# Zhurong.net
KiCad netlist of a schematic drawn in EasyEDA Pro
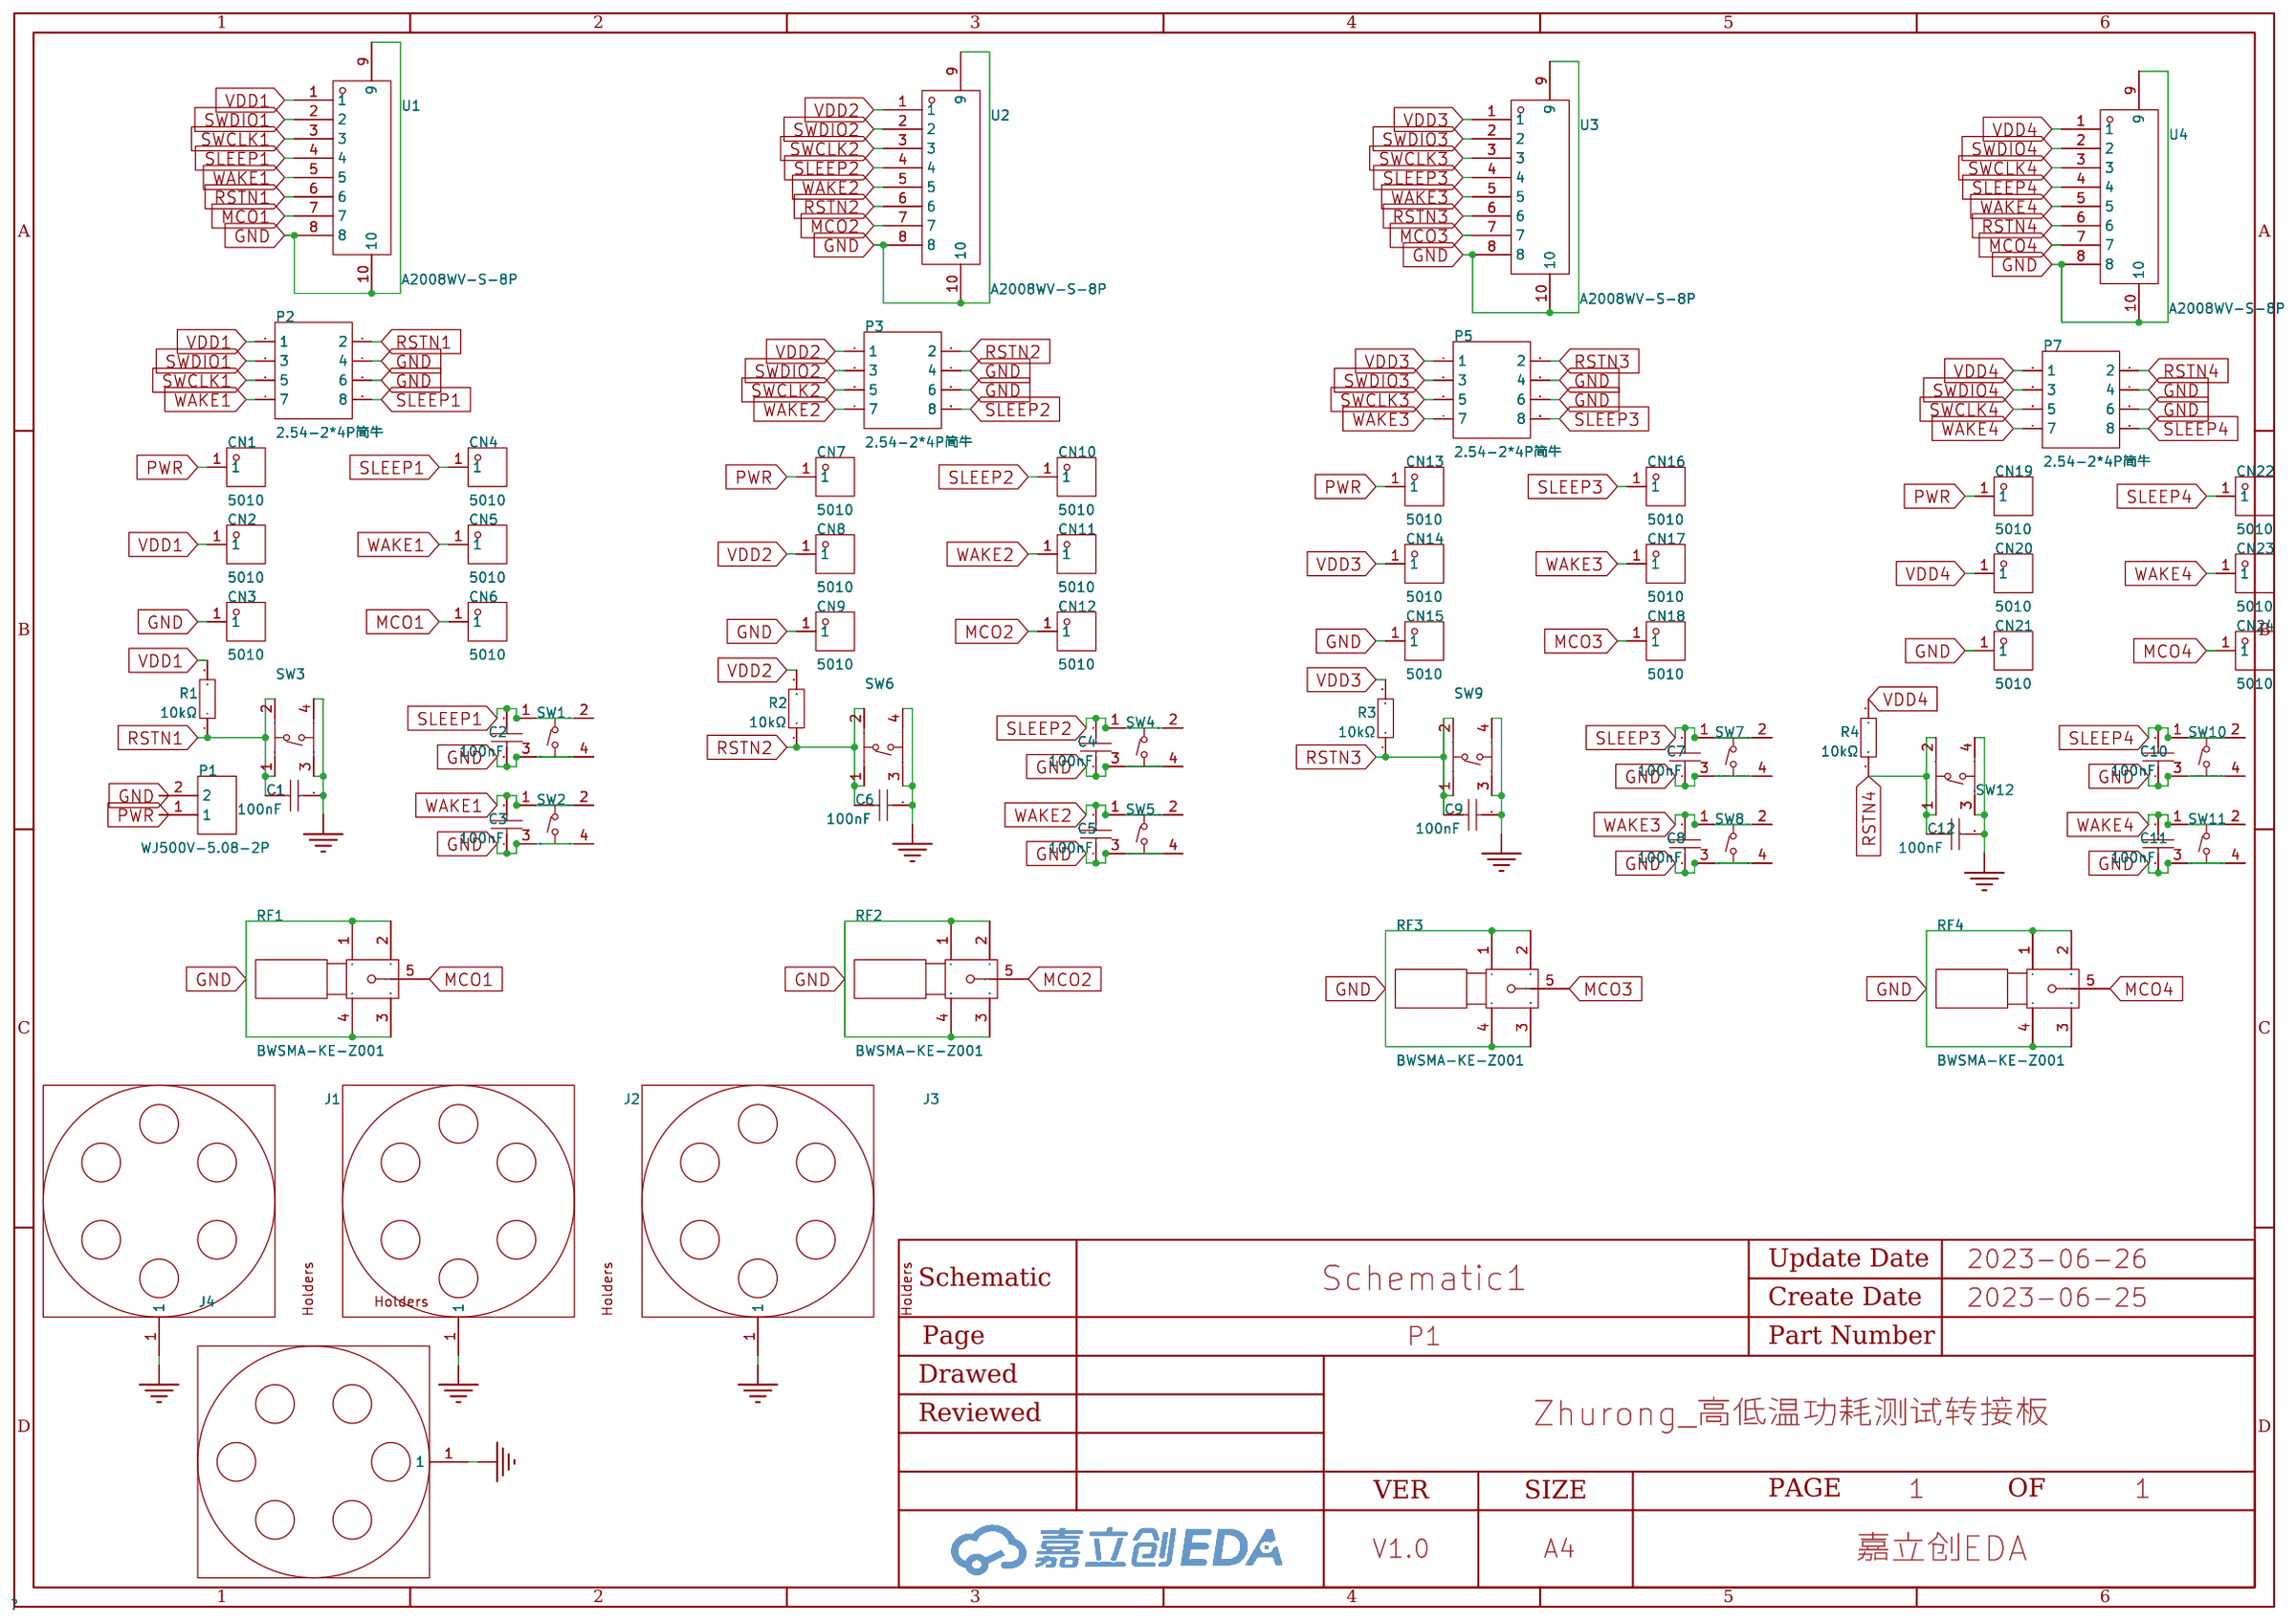
[diagram p0: schematic sheet]

(export (version "E")
  (design (tool "Eeschema 10.0.6"))
  (components
    (comp (ref "C1")
      (value "100nF")
      (footprint "easyedapro:C0603")
      (description "容值:100nF;精度:±10%;额定电压:50V;材质(温度系数):X7R;")
      (fields (field (name "Manufacturer Part") "0603B104K500NT") (field (name "Manufacturer") "FH(风华)"))
      (libsource (lib "easyedapro") (part "0603B104K500NT"))
    )
    (comp (ref "C2")
      (value "100nF")
      (footprint "easyedapro:C0603")
      (description "容值:100nF;精度:±10%;额定电压:50V;材质(温度系数):X7R;")
      (fields (field (name "Manufacturer Part") "0603B104K500NT") (field (name "Manufacturer") "FH(风华)"))
      (libsource (lib "easyedapro") (part "0603B104K500NT"))
    )
    (comp (ref "C3")
      (value "100nF")
      (footprint "easyedapro:C0603")
      (description "容值:100nF;精度:±10%;额定电压:50V;材质(温度系数):X7R;")
      (fields (field (name "Manufacturer Part") "0603B104K500NT") (field (name "Manufacturer") "FH(风华)"))
      (libsource (lib "easyedapro") (part "0603B104K500NT"))
    )
    (comp (ref "C4")
      (value "100nF")
      (footprint "easyedapro:C0603")
      (description "容值:100nF;精度:±10%;额定电压:50V;材质(温度系数):X7R;")
      (fields (field (name "Manufacturer Part") "0603B104K500NT") (field (name "Manufacturer") "FH(风华)"))
      (libsource (lib "easyedapro") (part "0603B104K500NT"))
    )
    (comp (ref "C5")
      (value "100nF")
      (footprint "easyedapro:C0603")
      (description "容值:100nF;精度:±10%;额定电压:50V;材质(温度系数):X7R;")
      (fields (field (name "Manufacturer Part") "0603B104K500NT") (field (name "Manufacturer") "FH(风华)"))
      (libsource (lib "easyedapro") (part "0603B104K500NT"))
    )
    (comp (ref "C6")
      (value "100nF")
      (footprint "easyedapro:C0603")
      (description "容值:100nF;精度:±10%;额定电压:50V;材质(温度系数):X7R;")
      (fields (field (name "Manufacturer Part") "0603B104K500NT") (field (name "Manufacturer") "FH(风华)"))
      (libsource (lib "easyedapro") (part "0603B104K500NT"))
    )
    (comp (ref "C7")
      (value "100nF")
      (footprint "easyedapro:C0603")
      (description "容值:100nF;精度:±10%;额定电压:50V;材质(温度系数):X7R;")
      (fields (field (name "Manufacturer Part") "0603B104K500NT") (field (name "Manufacturer") "FH(风华)"))
      (libsource (lib "easyedapro") (part "0603B104K500NT"))
    )
    (comp (ref "C8")
      (value "100nF")
      (footprint "easyedapro:C0603")
      (description "容值:100nF;精度:±10%;额定电压:50V;材质(温度系数):X7R;")
      (fields (field (name "Manufacturer Part") "0603B104K500NT") (field (name "Manufacturer") "FH(风华)"))
      (libsource (lib "easyedapro") (part "0603B104K500NT"))
    )
    (comp (ref "C9")
      (value "100nF")
      (footprint "easyedapro:C0603")
      (description "容值:100nF;精度:±10%;额定电压:50V;材质(温度系数):X7R;")
      (fields (field (name "Manufacturer Part") "0603B104K500NT") (field (name "Manufacturer") "FH(风华)"))
      (libsource (lib "easyedapro") (part "0603B104K500NT"))
    )
    (comp (ref "C10")
      (value "100nF")
      (footprint "easyedapro:C0603")
      (description "容值:100nF;精度:±10%;额定电压:50V;材质(温度系数):X7R;")
      (fields (field (name "Manufacturer Part") "0603B104K500NT") (field (name "Manufacturer") "FH(风华)"))
      (libsource (lib "easyedapro") (part "0603B104K500NT"))
    )
    (comp (ref "C11")
      (value "100nF")
      (footprint "easyedapro:C0603")
      (description "容值:100nF;精度:±10%;额定电压:50V;材质(温度系数):X7R;")
      (fields (field (name "Manufacturer Part") "0603B104K500NT") (field (name "Manufacturer") "FH(风华)"))
      (libsource (lib "easyedapro") (part "0603B104K500NT"))
    )
    (comp (ref "C12")
      (value "100nF")
      (footprint "easyedapro:C0603")
      (description "容值:100nF;精度:±10%;额定电压:50V;材质(温度系数):X7R;")
      (fields (field (name "Manufacturer Part") "0603B104K500NT") (field (name "Manufacturer") "FH(风华)"))
      (libsource (lib "easyedapro") (part "0603B104K500NT"))
    )
    (comp (ref "CN1")
      (value "5010")
      (footprint "easyedapro:TESTPOINT-TH_BD3.2")
      (fields (field (name "Manufacturer") "Keystone"))
      (libsource (lib "easyedapro") (part "5010"))
    )
    (comp (ref "CN2")
      (value "5010")
      (footprint "easyedapro:TESTPOINT-TH_BD3.2")
      (fields (field (name "Manufacturer") "Keystone"))
      (libsource (lib "easyedapro") (part "5010"))
    )
    (comp (ref "CN3")
      (value "5010")
      (footprint "easyedapro:TESTPOINT-TH_BD3.2")
      (fields (field (name "Manufacturer") "Keystone"))
      (libsource (lib "easyedapro") (part "5010"))
    )
    (comp (ref "CN4")
      (value "5010")
      (footprint "easyedapro:TESTPOINT-TH_BD3.2")
      (fields (field (name "Manufacturer") "Keystone"))
      (libsource (lib "easyedapro") (part "5010"))
    )
    (comp (ref "CN5")
      (value "5010")
      (footprint "easyedapro:TESTPOINT-TH_BD3.2")
      (fields (field (name "Manufacturer") "Keystone"))
      (libsource (lib "easyedapro") (part "5010"))
    )
    (comp (ref "CN6")
      (value "5010")
      (footprint "easyedapro:TESTPOINT-TH_BD3.2")
      (fields (field (name "Manufacturer") "Keystone"))
      (libsource (lib "easyedapro") (part "5010"))
    )
    (comp (ref "CN7")
      (value "5010")
      (footprint "easyedapro:TESTPOINT-TH_BD3.2")
      (fields (field (name "Manufacturer") "Keystone"))
      (libsource (lib "easyedapro") (part "5010"))
    )
    (comp (ref "CN8")
      (value "5010")
      (footprint "easyedapro:TESTPOINT-TH_BD3.2")
      (fields (field (name "Manufacturer") "Keystone"))
      (libsource (lib "easyedapro") (part "5010"))
    )
    (comp (ref "CN9")
      (value "5010")
      (footprint "easyedapro:TESTPOINT-TH_BD3.2")
      (fields (field (name "Manufacturer") "Keystone"))
      (libsource (lib "easyedapro") (part "5010"))
    )
    (comp (ref "CN10")
      (value "5010")
      (footprint "easyedapro:TESTPOINT-TH_BD3.2")
      (fields (field (name "Manufacturer") "Keystone"))
      (libsource (lib "easyedapro") (part "5010"))
    )
    (comp (ref "CN11")
      (value "5010")
      (footprint "easyedapro:TESTPOINT-TH_BD3.2")
      (fields (field (name "Manufacturer") "Keystone"))
      (libsource (lib "easyedapro") (part "5010"))
    )
    (comp (ref "CN12")
      (value "5010")
      (footprint "easyedapro:TESTPOINT-TH_BD3.2")
      (fields (field (name "Manufacturer") "Keystone"))
      (libsource (lib "easyedapro") (part "5010"))
    )
    (comp (ref "CN13")
      (value "5010")
      (footprint "easyedapro:TESTPOINT-TH_BD3.2")
      (fields (field (name "Manufacturer") "Keystone"))
      (libsource (lib "easyedapro") (part "5010"))
    )
    (comp (ref "CN14")
      (value "5010")
      (footprint "easyedapro:TESTPOINT-TH_BD3.2")
      (fields (field (name "Manufacturer") "Keystone"))
      (libsource (lib "easyedapro") (part "5010"))
    )
    (comp (ref "CN15")
      (value "5010")
      (footprint "easyedapro:TESTPOINT-TH_BD3.2")
      (fields (field (name "Manufacturer") "Keystone"))
      (libsource (lib "easyedapro") (part "5010"))
    )
    (comp (ref "CN16")
      (value "5010")
      (footprint "easyedapro:TESTPOINT-TH_BD3.2")
      (fields (field (name "Manufacturer") "Keystone"))
      (libsource (lib "easyedapro") (part "5010"))
    )
    (comp (ref "CN17")
      (value "5010")
      (footprint "easyedapro:TESTPOINT-TH_BD3.2")
      (fields (field (name "Manufacturer") "Keystone"))
      (libsource (lib "easyedapro") (part "5010"))
    )
    (comp (ref "CN18")
      (value "5010")
      (footprint "easyedapro:TESTPOINT-TH_BD3.2")
      (fields (field (name "Manufacturer") "Keystone"))
      (libsource (lib "easyedapro") (part "5010"))
    )
    (comp (ref "CN19")
      (value "5010")
      (footprint "easyedapro:TESTPOINT-TH_BD3.2")
      (fields (field (name "Manufacturer") "Keystone"))
      (libsource (lib "easyedapro") (part "5010"))
    )
    (comp (ref "CN20")
      (value "5010")
      (footprint "easyedapro:TESTPOINT-TH_BD3.2")
      (fields (field (name "Manufacturer") "Keystone"))
      (libsource (lib "easyedapro") (part "5010"))
    )
    (comp (ref "CN21")
      (value "5010")
      (footprint "easyedapro:TESTPOINT-TH_BD3.2")
      (fields (field (name "Manufacturer") "Keystone"))
      (libsource (lib "easyedapro") (part "5010"))
    )
    (comp (ref "CN22")
      (value "5010")
      (footprint "easyedapro:TESTPOINT-TH_BD3.2")
      (fields (field (name "Manufacturer") "Keystone"))
      (libsource (lib "easyedapro") (part "5010"))
    )
    (comp (ref "CN23")
      (value "5010")
      (footprint "easyedapro:TESTPOINT-TH_BD3.2")
      (fields (field (name "Manufacturer") "Keystone"))
      (libsource (lib "easyedapro") (part "5010"))
    )
    (comp (ref "CN24")
      (value "5010")
      (footprint "easyedapro:TESTPOINT-TH_BD3.2")
      (fields (field (name "Manufacturer") "Keystone"))
      (libsource (lib "easyedapro") (part "5010"))
    )
    (comp (ref "J1")
      (value "~")
      (footprint "easyedapro:DEMO板安装孔")
      (libsource (lib "easyedapro") (part "螺孔_3.1X6MM"))
    )
    (comp (ref "J2")
      (value "~")
      (footprint "easyedapro:DEMO板安装孔")
      (libsource (lib "easyedapro") (part "螺孔_3.1X6MM"))
    )
    (comp (ref "J3")
      (value "~")
      (footprint "easyedapro:DEMO板安装孔")
      (libsource (lib "easyedapro") (part "螺孔_3.1X6MM"))
    )
    (comp (ref "J4")
      (value "~")
      (footprint "easyedapro:DEMO板安装孔")
      (libsource (lib "easyedapro") (part "螺孔_3.1X6MM"))
    )
    (comp (ref "P1")
      (value "WJ500V-5.08-2P")
      (footprint "easyedapro:CONN-TH_2P-P5.00_WJ500V-5.08-2P")
      (fields (field (name "Manufacturer") "KANGNEX(康奈克斯电气)"))
      (libsource (lib "easyedapro") (part "WJ500V-5.08-2P-14-00A"))
    )
    (comp (ref "P2")
      (value "2.54-2*4P简牛")
      (footprint "easyedapro:IDC-TH_8P-P2.54-V-R2-C4-S2.54")
      (description "连接器类型:简牛座;每排PIN数:4;结构:2x4P;排数:2;间距:2.54mm;行距:2.54mm;封装形式:直插;触头材质:-;触头镀层:-;")
      (fields (field (name "Manufacturer") "BOOMELE(博穆精密)"))
      (libsource (lib "easyedapro") (part "HDR-IDC-2.54-2X4P"))
    )
    (comp (ref "P3")
      (value "2.54-2*4P简牛")
      (footprint "easyedapro:IDC-TH_8P-P2.54-V-R2-C4-S2.54")
      (description "连接器类型:简牛座;每排PIN数:4;结构:2x4P;排数:2;间距:2.54mm;行距:2.54mm;封装形式:直插;触头材质:-;触头镀层:-;")
      (fields (field (name "Manufacturer") "BOOMELE(博穆精密)"))
      (libsource (lib "easyedapro") (part "HDR-IDC-2.54-2X4P"))
    )
    (comp (ref "P5")
      (value "2.54-2*4P简牛")
      (footprint "easyedapro:IDC-TH_8P-P2.54-V-R2-C4-S2.54")
      (description "连接器类型:简牛座;每排PIN数:4;结构:2x4P;排数:2;间距:2.54mm;行距:2.54mm;封装形式:直插;触头材质:-;触头镀层:-;")
      (fields (field (name "Manufacturer") "BOOMELE(博穆精密)"))
      (libsource (lib "easyedapro") (part "HDR-IDC-2.54-2X4P"))
    )
    (comp (ref "P7")
      (value "2.54-2*4P简牛")
      (footprint "easyedapro:IDC-TH_8P-P2.54-V-R2-C4-S2.54")
      (description "连接器类型:简牛座;每排PIN数:4;结构:2x4P;排数:2;间距:2.54mm;行距:2.54mm;封装形式:直插;触头材质:-;触头镀层:-;")
      (fields (field (name "Manufacturer") "BOOMELE(博穆精密)"))
      (libsource (lib "easyedapro") (part "HDR-IDC-2.54-2X4P"))
    )
    (comp (ref "R1")
      (value "10kΩ")
      (footprint "easyedapro:R0805")
      (description "阻值:10kΩ;精度:±1%;功率:125mW;温度系数:±100ppm/°C;最大工作电压:150V;工作温度范围:-55°C~+155°C;")
      (fields (field (name "Manufacturer Part") "RC0805FR-0710KL") (field (name "Manufacturer") "YAGEO(国巨)"))
      (libsource (lib "easyedapro") (part "RC0805FR-0710KL"))
    )
    (comp (ref "R2")
      (value "10kΩ")
      (footprint "easyedapro:R0805")
      (description "阻值:10kΩ;精度:±1%;功率:125mW;温度系数:±100ppm/°C;最大工作电压:150V;工作温度范围:-55°C~+155°C;")
      (fields (field (name "Manufacturer Part") "RC0805FR-0710KL") (field (name "Manufacturer") "YAGEO(国巨)"))
      (libsource (lib "easyedapro") (part "RC0805FR-0710KL"))
    )
    (comp (ref "R3")
      (value "10kΩ")
      (footprint "easyedapro:R0805")
      (description "阻值:10kΩ;精度:±1%;功率:125mW;温度系数:±100ppm/°C;最大工作电压:150V;工作温度范围:-55°C~+155°C;")
      (fields (field (name "Manufacturer Part") "RC0805FR-0710KL") (field (name "Manufacturer") "YAGEO(国巨)"))
      (libsource (lib "easyedapro") (part "RC0805FR-0710KL"))
    )
    (comp (ref "R4")
      (value "10kΩ")
      (footprint "easyedapro:R0805")
      (description "阻值:10kΩ;精度:±1%;功率:125mW;温度系数:±100ppm/°C;最大工作电压:150V;工作温度范围:-55°C~+155°C;")
      (fields (field (name "Manufacturer Part") "RC0805FR-0710KL") (field (name "Manufacturer") "YAGEO(国巨)"))
      (libsource (lib "easyedapro") (part "RC0805FR-0710KL"))
    )
    (comp (ref "RF1")
      (value "BWSMA-KE-Z001")
      (footprint "easyedapro:SMA-TH_BWSMA-KE-Z001")
      (description "连接器类型:板端;射频系列:SMA;接口类型:内孔;端口数量:1;阻抗:50Ω;频率-最大值:12.4GHz;样式:正脚;接口直径:-;接口长度/高度:-;工作温度范围:-65°C~+165°C;")
      (fields (field (name "Manufacturer") "BAT WIRELESS(蝙蝠无线)"))
      (libsource (lib "easyedapro") (part "BWSMA-KE-Z001"))
    )
    (comp (ref "RF2")
      (value "BWSMA-KE-Z001")
      (footprint "easyedapro:SMA-TH_BWSMA-KE-Z001")
      (description "连接器类型:板端;射频系列:SMA;接口类型:内孔;端口数量:1;阻抗:50Ω;频率-最大值:12.4GHz;样式:正脚;接口直径:-;接口长度/高度:-;工作温度范围:-65°C~+165°C;")
      (fields (field (name "Manufacturer") "BAT WIRELESS(蝙蝠无线)"))
      (libsource (lib "easyedapro") (part "BWSMA-KE-Z001"))
    )
    (comp (ref "RF3")
      (value "BWSMA-KE-Z001")
      (footprint "easyedapro:SMA-TH_BWSMA-KE-Z001")
      (description "连接器类型:板端;射频系列:SMA;接口类型:内孔;端口数量:1;阻抗:50Ω;频率-最大值:12.4GHz;样式:正脚;接口直径:-;接口长度/高度:-;工作温度范围:-65°C~+165°C;")
      (fields (field (name "Manufacturer") "BAT WIRELESS(蝙蝠无线)"))
      (libsource (lib "easyedapro") (part "BWSMA-KE-Z001"))
    )
    (comp (ref "RF4")
      (value "BWSMA-KE-Z001")
      (footprint "easyedapro:SMA-TH_BWSMA-KE-Z001")
      (description "连接器类型:板端;射频系列:SMA;接口类型:内孔;端口数量:1;阻抗:50Ω;频率-最大值:12.4GHz;样式:正脚;接口直径:-;接口长度/高度:-;工作温度范围:-65°C~+165°C;")
      (fields (field (name "Manufacturer") "BAT WIRELESS(蝙蝠无线)"))
      (libsource (lib "easyedapro") (part "BWSMA-KE-Z001"))
    )
    (comp (ref "SW1")
      (value "YTS-C015-2K")
      (footprint "easyedapro:SW-SMD_4P-L4.5-W4.5-P3.00-LS6.8")
      (description "触点电流:50mA;额定电压(DC):12V;绝缘电阻:100MΩ;电路结构:单刀单掷;安装方式:立贴;作用力:260gf@±50gf;机械寿命:5万次;带支架:否;")
      (fields (field (name "Manufacturer") "YIYUAN(怡远)"))
      (libsource (lib "easyedapro") (part "YTS-C015-2K"))
    )
    (comp (ref "SW2")
      (value "YTS-C015-2K")
      (footprint "easyedapro:SW-SMD_4P-L4.5-W4.5-P3.00-LS6.8")
      (description "触点电流:50mA;额定电压(DC):12V;绝缘电阻:100MΩ;电路结构:单刀单掷;安装方式:立贴;作用力:260gf@±50gf;机械寿命:5万次;带支架:否;")
      (fields (field (name "Manufacturer") "YIYUAN(怡远)"))
      (libsource (lib "easyedapro") (part "YTS-C015-2K"))
    )
    (comp (ref "SW3")
      (value "YTS-C015-2K")
      (footprint "easyedapro:SW-SMD_4P-L4.5-W4.5-P3.00-LS6.8")
      (description "触点电流:50mA;额定电压(DC):12V;绝缘电阻:100MΩ;电路结构:单刀单掷;安装方式:立贴;作用力:260gf@±50gf;机械寿命:5万次;带支架:否;")
      (fields (field (name "Manufacturer") "YIYUAN(怡远)"))
      (libsource (lib "easyedapro") (part "YTS-C015-2K"))
    )
    (comp (ref "SW4")
      (value "YTS-C015-2K")
      (footprint "easyedapro:SW-SMD_4P-L4.5-W4.5-P3.00-LS6.8")
      (description "触点电流:50mA;额定电压(DC):12V;绝缘电阻:100MΩ;电路结构:单刀单掷;安装方式:立贴;作用力:260gf@±50gf;机械寿命:5万次;带支架:否;")
      (fields (field (name "Manufacturer") "YIYUAN(怡远)"))
      (libsource (lib "easyedapro") (part "YTS-C015-2K"))
    )
    (comp (ref "SW5")
      (value "YTS-C015-2K")
      (footprint "easyedapro:SW-SMD_4P-L4.5-W4.5-P3.00-LS6.8")
      (description "触点电流:50mA;额定电压(DC):12V;绝缘电阻:100MΩ;电路结构:单刀单掷;安装方式:立贴;作用力:260gf@±50gf;机械寿命:5万次;带支架:否;")
      (fields (field (name "Manufacturer") "YIYUAN(怡远)"))
      (libsource (lib "easyedapro") (part "YTS-C015-2K"))
    )
    (comp (ref "SW6")
      (value "YTS-C015-2K")
      (footprint "easyedapro:SW-SMD_4P-L4.5-W4.5-P3.00-LS6.8")
      (description "触点电流:50mA;额定电压(DC):12V;绝缘电阻:100MΩ;电路结构:单刀单掷;安装方式:立贴;作用力:260gf@±50gf;机械寿命:5万次;带支架:否;")
      (fields (field (name "Manufacturer") "YIYUAN(怡远)"))
      (libsource (lib "easyedapro") (part "YTS-C015-2K"))
    )
    (comp (ref "SW7")
      (value "YTS-C015-2K")
      (footprint "easyedapro:SW-SMD_4P-L4.5-W4.5-P3.00-LS6.8")
      (description "触点电流:50mA;额定电压(DC):12V;绝缘电阻:100MΩ;电路结构:单刀单掷;安装方式:立贴;作用力:260gf@±50gf;机械寿命:5万次;带支架:否;")
      (fields (field (name "Manufacturer") "YIYUAN(怡远)"))
      (libsource (lib "easyedapro") (part "YTS-C015-2K"))
    )
    (comp (ref "SW8")
      (value "YTS-C015-2K")
      (footprint "easyedapro:SW-SMD_4P-L4.5-W4.5-P3.00-LS6.8")
      (description "触点电流:50mA;额定电压(DC):12V;绝缘电阻:100MΩ;电路结构:单刀单掷;安装方式:立贴;作用力:260gf@±50gf;机械寿命:5万次;带支架:否;")
      (fields (field (name "Manufacturer") "YIYUAN(怡远)"))
      (libsource (lib "easyedapro") (part "YTS-C015-2K"))
    )
    (comp (ref "SW9")
      (value "YTS-C015-2K")
      (footprint "easyedapro:SW-SMD_4P-L4.5-W4.5-P3.00-LS6.8")
      (description "触点电流:50mA;额定电压(DC):12V;绝缘电阻:100MΩ;电路结构:单刀单掷;安装方式:立贴;作用力:260gf@±50gf;机械寿命:5万次;带支架:否;")
      (fields (field (name "Manufacturer") "YIYUAN(怡远)"))
      (libsource (lib "easyedapro") (part "YTS-C015-2K"))
    )
    (comp (ref "SW10")
      (value "YTS-C015-2K")
      (footprint "easyedapro:SW-SMD_4P-L4.5-W4.5-P3.00-LS6.8")
      (description "触点电流:50mA;额定电压(DC):12V;绝缘电阻:100MΩ;电路结构:单刀单掷;安装方式:立贴;作用力:260gf@±50gf;机械寿命:5万次;带支架:否;")
      (fields (field (name "Manufacturer") "YIYUAN(怡远)"))
      (libsource (lib "easyedapro") (part "YTS-C015-2K"))
    )
    (comp (ref "SW11")
      (value "YTS-C015-2K")
      (footprint "easyedapro:SW-SMD_4P-L4.5-W4.5-P3.00-LS6.8")
      (description "触点电流:50mA;额定电压(DC):12V;绝缘电阻:100MΩ;电路结构:单刀单掷;安装方式:立贴;作用力:260gf@±50gf;机械寿命:5万次;带支架:否;")
      (fields (field (name "Manufacturer") "YIYUAN(怡远)"))
      (libsource (lib "easyedapro") (part "YTS-C015-2K"))
    )
    (comp (ref "SW12")
      (value "YTS-C015-2K")
      (footprint "easyedapro:SW-SMD_4P-L4.5-W4.5-P3.00-LS6.8")
      (description "触点电流:50mA;额定电压(DC):12V;绝缘电阻:100MΩ;电路结构:单刀单掷;安装方式:立贴;作用力:260gf@±50gf;机械寿命:5万次;带支架:否;")
      (fields (field (name "Manufacturer") "YIYUAN(怡远)"))
      (libsource (lib "easyedapro") (part "YTS-C015-2K"))
    )
    (comp (ref "U1")
      (value "A2008WV-S-8P")
      (footprint "easyedapro:CONN-SMD_A2008WV-S-8P")
      (description "参考系列:PH;间距:2mm;插针结构:1x8P;排数:1;每排PIN数:8;行距:-;安装方式:-;触头材质:黄铜;")
      (fields (field (name "Manufacturer") "CJT(长江连接器)"))
      (libsource (lib "easyedapro") (part "A2008WV-S-8P"))
    )
    (comp (ref "U2")
      (value "A2008WV-S-8P")
      (footprint "easyedapro:CONN-SMD_A2008WV-S-8P")
      (description "参考系列:PH;间距:2mm;插针结构:1x8P;排数:1;每排PIN数:8;行距:-;安装方式:-;触头材质:黄铜;")
      (fields (field (name "Manufacturer") "CJT(长江连接器)"))
      (libsource (lib "easyedapro") (part "A2008WV-S-8P"))
    )
    (comp (ref "U3")
      (value "A2008WV-S-8P")
      (footprint "easyedapro:CONN-SMD_A2008WV-S-8P")
      (description "参考系列:PH;间距:2mm;插针结构:1x8P;排数:1;每排PIN数:8;行距:-;安装方式:-;触头材质:黄铜;")
      (fields (field (name "Manufacturer") "CJT(长江连接器)"))
      (libsource (lib "easyedapro") (part "A2008WV-S-8P"))
    )
    (comp (ref "U4")
      (value "A2008WV-S-8P")
      (footprint "easyedapro:CONN-SMD_A2008WV-S-8P")
      (description "参考系列:PH;间距:2mm;插针结构:1x8P;排数:1;每排PIN数:8;行距:-;安装方式:-;触头材质:黄铜;")
      (fields (field (name "Manufacturer") "CJT(长江连接器)"))
      (libsource (lib "easyedapro") (part "A2008WV-S-8P"))
    )
  )
  (nets
    (net (code "1") (name "GND") (class "Default")
      (node (ref "C1") (pin "2") (pinfunction "2_2") (pintype "input"))
      (node (ref "C10") (pin "1") (pinfunction "1_1") (pintype "input"))
      (node (ref "C11") (pin "1") (pinfunction "1_1") (pintype "input"))
      (node (ref "C12") (pin "2") (pinfunction "2_2") (pintype "input"))
      (node (ref "C2") (pin "1") (pinfunction "1_1") (pintype "input"))
      (node (ref "C3") (pin "1") (pinfunction "1_1") (pintype "input"))
      (node (ref "C4") (pin "1") (pinfunction "1_1") (pintype "input"))
      (node (ref "C5") (pin "1") (pinfunction "1_1") (pintype "input"))
      (node (ref "C6") (pin "2") (pinfunction "2_2") (pintype "input"))
      (node (ref "C7") (pin "1") (pinfunction "1_1") (pintype "input"))
      (node (ref "C8") (pin "1") (pinfunction "1_1") (pintype "input"))
      (node (ref "C9") (pin "2") (pinfunction "2_2") (pintype "input"))
      (node (ref "CN15") (pin "1") (pinfunction "1_1") (pintype "input"))
      (node (ref "CN21") (pin "1") (pinfunction "1_1") (pintype "input"))
      (node (ref "CN3") (pin "1") (pinfunction "1_1") (pintype "input"))
      (node (ref "CN9") (pin "1") (pinfunction "1_1") (pintype "input"))
      (node (ref "J1") (pin "1") (pinfunction "1_1") (pintype "input"))
      (node (ref "J2") (pin "1") (pinfunction "1_1") (pintype "input"))
      (node (ref "J3") (pin "1") (pinfunction "1_1") (pintype "input"))
      (node (ref "J4") (pin "1") (pinfunction "1_1") (pintype "input"))
      (node (ref "P1") (pin "2") (pinfunction "2_2") (pintype "input"))
      (node (ref "P2") (pin "4") (pinfunction "4_4") (pintype "input"))
      (node (ref "P2") (pin "6") (pinfunction "6_6") (pintype "input"))
      (node (ref "P3") (pin "4") (pinfunction "4_4") (pintype "input"))
      (node (ref "P3") (pin "6") (pinfunction "6_6") (pintype "input"))
      (node (ref "P5") (pin "4") (pinfunction "4_4") (pintype "input"))
      (node (ref "P5") (pin "6") (pinfunction "6_6") (pintype "input"))
      (node (ref "P7") (pin "4") (pinfunction "4_4") (pintype "input"))
      (node (ref "P7") (pin "6") (pinfunction "6_6") (pintype "input"))
      (node (ref "RF1") (pin "1") (pinfunction "1_1") (pintype "input"))
      (node (ref "RF1") (pin "2") (pinfunction "2_2") (pintype "input"))
      (node (ref "RF1") (pin "3") (pinfunction "3_3") (pintype "input"))
      (node (ref "RF1") (pin "4") (pinfunction "4_4") (pintype "input"))
      (node (ref "RF2") (pin "1") (pinfunction "1_1") (pintype "input"))
      (node (ref "RF2") (pin "2") (pinfunction "2_2") (pintype "input"))
      (node (ref "RF2") (pin "3") (pinfunction "3_3") (pintype "input"))
      (node (ref "RF2") (pin "4") (pinfunction "4_4") (pintype "input"))
      (node (ref "RF3") (pin "1") (pinfunction "1_1") (pintype "input"))
      (node (ref "RF3") (pin "2") (pinfunction "2_2") (pintype "input"))
      (node (ref "RF3") (pin "3") (pinfunction "3_3") (pintype "input"))
      (node (ref "RF3") (pin "4") (pinfunction "4_4") (pintype "input"))
      (node (ref "RF4") (pin "1") (pinfunction "1_1") (pintype "input"))
      (node (ref "RF4") (pin "2") (pinfunction "2_2") (pintype "input"))
      (node (ref "RF4") (pin "3") (pinfunction "3_3") (pintype "input"))
      (node (ref "RF4") (pin "4") (pinfunction "4_4") (pintype "input"))
      (node (ref "SW1") (pin "3") (pinfunction "3_3") (pintype "input"))
      (node (ref "SW1") (pin "4") (pinfunction "4_4") (pintype "input"))
      (node (ref "SW10") (pin "3") (pinfunction "3_3") (pintype "input"))
      (node (ref "SW10") (pin "4") (pinfunction "4_4") (pintype "input"))
      (node (ref "SW11") (pin "3") (pinfunction "3_3") (pintype "input"))
      (node (ref "SW11") (pin "4") (pinfunction "4_4") (pintype "input"))
      (node (ref "SW12") (pin "3") (pinfunction "3_3") (pintype "input"))
      (node (ref "SW12") (pin "4") (pinfunction "4_4") (pintype "input"))
      (node (ref "SW2") (pin "3") (pinfunction "3_3") (pintype "input"))
      (node (ref "SW2") (pin "4") (pinfunction "4_4") (pintype "input"))
      (node (ref "SW3") (pin "3") (pinfunction "3_3") (pintype "input"))
      (node (ref "SW3") (pin "4") (pinfunction "4_4") (pintype "input"))
      (node (ref "SW4") (pin "3") (pinfunction "3_3") (pintype "input"))
      (node (ref "SW4") (pin "4") (pinfunction "4_4") (pintype "input"))
      (node (ref "SW5") (pin "3") (pinfunction "3_3") (pintype "input"))
      (node (ref "SW5") (pin "4") (pinfunction "4_4") (pintype "input"))
      (node (ref "SW6") (pin "3") (pinfunction "3_3") (pintype "input"))
      (node (ref "SW6") (pin "4") (pinfunction "4_4") (pintype "input"))
      (node (ref "SW7") (pin "3") (pinfunction "3_3") (pintype "input"))
      (node (ref "SW7") (pin "4") (pinfunction "4_4") (pintype "input"))
      (node (ref "SW8") (pin "3") (pinfunction "3_3") (pintype "input"))
      (node (ref "SW8") (pin "4") (pinfunction "4_4") (pintype "input"))
      (node (ref "SW9") (pin "3") (pinfunction "3_3") (pintype "input"))
      (node (ref "SW9") (pin "4") (pinfunction "4_4") (pintype "input"))
      (node (ref "U1") (pin "10") (pinfunction "10_10") (pintype "input"))
      (node (ref "U1") (pin "8") (pinfunction "8_8") (pintype "input"))
      (node (ref "U1") (pin "9") (pinfunction "9_9") (pintype "input"))
      (node (ref "U2") (pin "10") (pinfunction "10_10") (pintype "input"))
      (node (ref "U2") (pin "8") (pinfunction "8_8") (pintype "input"))
      (node (ref "U2") (pin "9") (pinfunction "9_9") (pintype "input"))
      (node (ref "U3") (pin "10") (pinfunction "10_10") (pintype "input"))
      (node (ref "U3") (pin "8") (pinfunction "8_8") (pintype "input"))
      (node (ref "U3") (pin "9") (pinfunction "9_9") (pintype "input"))
      (node (ref "U4") (pin "10") (pinfunction "10_10") (pintype "input"))
      (node (ref "U4") (pin "8") (pinfunction "8_8") (pintype "input"))
      (node (ref "U4") (pin "9") (pinfunction "9_9") (pintype "input"))
    )
    (net (code "2") (name "MCO1") (class "Default")
      (node (ref "CN6") (pin "1") (pinfunction "1_1") (pintype "input"))
      (node (ref "RF1") (pin "5") (pinfunction "5_5") (pintype "input"))
      (node (ref "U1") (pin "7") (pinfunction "7_7") (pintype "input"))
    )
    (net (code "3") (name "MCO2") (class "Default")
      (node (ref "CN12") (pin "1") (pinfunction "1_1") (pintype "input"))
      (node (ref "RF2") (pin "5") (pinfunction "5_5") (pintype "input"))
      (node (ref "U2") (pin "7") (pinfunction "7_7") (pintype "input"))
    )
    (net (code "4") (name "MCO3") (class "Default")
      (node (ref "CN18") (pin "1") (pinfunction "1_1") (pintype "input"))
      (node (ref "RF3") (pin "5") (pinfunction "5_5") (pintype "input"))
      (node (ref "U3") (pin "7") (pinfunction "7_7") (pintype "input"))
    )
    (net (code "5") (name "MCO4") (class "Default")
      (node (ref "CN24") (pin "1") (pinfunction "1_1") (pintype "input"))
      (node (ref "RF4") (pin "5") (pinfunction "5_5") (pintype "input"))
      (node (ref "U4") (pin "7") (pinfunction "7_7") (pintype "input"))
    )
    (net (code "6") (name "PWR") (class "Default")
      (node (ref "CN1") (pin "1") (pinfunction "1_1") (pintype "input"))
      (node (ref "CN13") (pin "1") (pinfunction "1_1") (pintype "input"))
      (node (ref "CN19") (pin "1") (pinfunction "1_1") (pintype "input"))
      (node (ref "CN7") (pin "1") (pinfunction "1_1") (pintype "input"))
      (node (ref "P1") (pin "1") (pinfunction "1_1") (pintype "input"))
    )
    (net (code "7") (name "RSTN1") (class "Default")
      (node (ref "C1") (pin "1") (pinfunction "1_1") (pintype "input"))
      (node (ref "P2") (pin "2") (pinfunction "2_2") (pintype "input"))
      (node (ref "R1") (pin "1") (pinfunction "1_1") (pintype "input"))
      (node (ref "SW3") (pin "1") (pinfunction "1_1") (pintype "input"))
      (node (ref "SW3") (pin "2") (pinfunction "2_2") (pintype "input"))
      (node (ref "U1") (pin "6") (pinfunction "6_6") (pintype "input"))
    )
    (net (code "8") (name "RSTN2") (class "Default")
      (node (ref "C6") (pin "1") (pinfunction "1_1") (pintype "input"))
      (node (ref "P3") (pin "2") (pinfunction "2_2") (pintype "input"))
      (node (ref "R2") (pin "1") (pinfunction "1_1") (pintype "input"))
      (node (ref "SW6") (pin "1") (pinfunction "1_1") (pintype "input"))
      (node (ref "SW6") (pin "2") (pinfunction "2_2") (pintype "input"))
      (node (ref "U2") (pin "6") (pinfunction "6_6") (pintype "input"))
    )
    (net (code "9") (name "RSTN3") (class "Default")
      (node (ref "C9") (pin "1") (pinfunction "1_1") (pintype "input"))
      (node (ref "P5") (pin "2") (pinfunction "2_2") (pintype "input"))
      (node (ref "R3") (pin "1") (pinfunction "1_1") (pintype "input"))
      (node (ref "SW9") (pin "1") (pinfunction "1_1") (pintype "input"))
      (node (ref "SW9") (pin "2") (pinfunction "2_2") (pintype "input"))
      (node (ref "U3") (pin "6") (pinfunction "6_6") (pintype "input"))
    )
    (net (code "10") (name "RSTN4") (class "Default")
      (node (ref "C12") (pin "1") (pinfunction "1_1") (pintype "input"))
      (node (ref "P7") (pin "2") (pinfunction "2_2") (pintype "input"))
      (node (ref "R4") (pin "1") (pinfunction "1_1") (pintype "input"))
      (node (ref "SW12") (pin "1") (pinfunction "1_1") (pintype "input"))
      (node (ref "SW12") (pin "2") (pinfunction "2_2") (pintype "input"))
      (node (ref "U4") (pin "6") (pinfunction "6_6") (pintype "input"))
    )
    (net (code "11") (name "SLEEP1") (class "Default")
      (node (ref "C2") (pin "2") (pinfunction "2_2") (pintype "input"))
      (node (ref "CN4") (pin "1") (pinfunction "1_1") (pintype "input"))
      (node (ref "P2") (pin "8") (pinfunction "8_8") (pintype "input"))
      (node (ref "SW1") (pin "1") (pinfunction "1_1") (pintype "input"))
      (node (ref "SW1") (pin "2") (pinfunction "2_2") (pintype "input"))
      (node (ref "U1") (pin "4") (pinfunction "4_4") (pintype "input"))
    )
    (net (code "12") (name "SLEEP2") (class "Default")
      (node (ref "C4") (pin "2") (pinfunction "2_2") (pintype "input"))
      (node (ref "CN10") (pin "1") (pinfunction "1_1") (pintype "input"))
      (node (ref "P3") (pin "8") (pinfunction "8_8") (pintype "input"))
      (node (ref "SW4") (pin "1") (pinfunction "1_1") (pintype "input"))
      (node (ref "SW4") (pin "2") (pinfunction "2_2") (pintype "input"))
      (node (ref "U2") (pin "4") (pinfunction "4_4") (pintype "input"))
    )
    (net (code "13") (name "SLEEP3") (class "Default")
      (node (ref "C7") (pin "2") (pinfunction "2_2") (pintype "input"))
      (node (ref "CN16") (pin "1") (pinfunction "1_1") (pintype "input"))
      (node (ref "P5") (pin "8") (pinfunction "8_8") (pintype "input"))
      (node (ref "SW7") (pin "1") (pinfunction "1_1") (pintype "input"))
      (node (ref "SW7") (pin "2") (pinfunction "2_2") (pintype "input"))
      (node (ref "U3") (pin "4") (pinfunction "4_4") (pintype "input"))
    )
    (net (code "14") (name "SLEEP4") (class "Default")
      (node (ref "C10") (pin "2") (pinfunction "2_2") (pintype "input"))
      (node (ref "CN22") (pin "1") (pinfunction "1_1") (pintype "input"))
      (node (ref "P7") (pin "8") (pinfunction "8_8") (pintype "input"))
      (node (ref "SW10") (pin "1") (pinfunction "1_1") (pintype "input"))
      (node (ref "SW10") (pin "2") (pinfunction "2_2") (pintype "input"))
      (node (ref "U4") (pin "4") (pinfunction "4_4") (pintype "input"))
    )
    (net (code "15") (name "SWCLK1") (class "Default")
      (node (ref "P2") (pin "5") (pinfunction "5_5") (pintype "input"))
      (node (ref "U1") (pin "3") (pinfunction "3_3") (pintype "input"))
    )
    (net (code "16") (name "SWCLK2") (class "Default")
      (node (ref "P3") (pin "5") (pinfunction "5_5") (pintype "input"))
      (node (ref "U2") (pin "3") (pinfunction "3_3") (pintype "input"))
    )
    (net (code "17") (name "SWCLK3") (class "Default")
      (node (ref "P5") (pin "5") (pinfunction "5_5") (pintype "input"))
      (node (ref "U3") (pin "3") (pinfunction "3_3") (pintype "input"))
    )
    (net (code "18") (name "SWCLK4") (class "Default")
      (node (ref "P7") (pin "5") (pinfunction "5_5") (pintype "input"))
      (node (ref "U4") (pin "3") (pinfunction "3_3") (pintype "input"))
    )
    (net (code "19") (name "SWDIO1") (class "Default")
      (node (ref "P2") (pin "3") (pinfunction "3_3") (pintype "input"))
      (node (ref "U1") (pin "2") (pinfunction "2_2") (pintype "input"))
    )
    (net (code "20") (name "SWDIO2") (class "Default")
      (node (ref "P3") (pin "3") (pinfunction "3_3") (pintype "input"))
      (node (ref "U2") (pin "2") (pinfunction "2_2") (pintype "input"))
    )
    (net (code "21") (name "SWDIO3") (class "Default")
      (node (ref "P5") (pin "3") (pinfunction "3_3") (pintype "input"))
      (node (ref "U3") (pin "2") (pinfunction "2_2") (pintype "input"))
    )
    (net (code "22") (name "SWDIO4") (class "Default")
      (node (ref "P7") (pin "3") (pinfunction "3_3") (pintype "input"))
      (node (ref "U4") (pin "2") (pinfunction "2_2") (pintype "input"))
    )
    (net (code "23") (name "VDD1") (class "Default")
      (node (ref "CN2") (pin "1") (pinfunction "1_1") (pintype "input"))
      (node (ref "P2") (pin "1") (pinfunction "1_1") (pintype "input"))
      (node (ref "R1") (pin "2") (pinfunction "2_2") (pintype "input"))
      (node (ref "U1") (pin "1") (pinfunction "1_1") (pintype "input"))
    )
    (net (code "24") (name "VDD2") (class "Default")
      (node (ref "CN8") (pin "1") (pinfunction "1_1") (pintype "input"))
      (node (ref "P3") (pin "1") (pinfunction "1_1") (pintype "input"))
      (node (ref "R2") (pin "2") (pinfunction "2_2") (pintype "input"))
      (node (ref "U2") (pin "1") (pinfunction "1_1") (pintype "input"))
    )
    (net (code "25") (name "VDD3") (class "Default")
      (node (ref "CN14") (pin "1") (pinfunction "1_1") (pintype "input"))
      (node (ref "P5") (pin "1") (pinfunction "1_1") (pintype "input"))
      (node (ref "R3") (pin "2") (pinfunction "2_2") (pintype "input"))
      (node (ref "U3") (pin "1") (pinfunction "1_1") (pintype "input"))
    )
    (net (code "26") (name "VDD4") (class "Default")
      (node (ref "CN20") (pin "1") (pinfunction "1_1") (pintype "input"))
      (node (ref "P7") (pin "1") (pinfunction "1_1") (pintype "input"))
      (node (ref "R4") (pin "2") (pinfunction "2_2") (pintype "input"))
      (node (ref "U4") (pin "1") (pinfunction "1_1") (pintype "input"))
    )
    (net (code "27") (name "WAKE1") (class "Default")
      (node (ref "C3") (pin "2") (pinfunction "2_2") (pintype "input"))
      (node (ref "CN5") (pin "1") (pinfunction "1_1") (pintype "input"))
      (node (ref "P2") (pin "7") (pinfunction "7_7") (pintype "input"))
      (node (ref "SW2") (pin "1") (pinfunction "1_1") (pintype "input"))
      (node (ref "SW2") (pin "2") (pinfunction "2_2") (pintype "input"))
      (node (ref "U1") (pin "5") (pinfunction "5_5") (pintype "input"))
    )
    (net (code "28") (name "WAKE2") (class "Default")
      (node (ref "C5") (pin "2") (pinfunction "2_2") (pintype "input"))
      (node (ref "CN11") (pin "1") (pinfunction "1_1") (pintype "input"))
      (node (ref "P3") (pin "7") (pinfunction "7_7") (pintype "input"))
      (node (ref "SW5") (pin "1") (pinfunction "1_1") (pintype "input"))
      (node (ref "SW5") (pin "2") (pinfunction "2_2") (pintype "input"))
      (node (ref "U2") (pin "5") (pinfunction "5_5") (pintype "input"))
    )
    (net (code "29") (name "WAKE3") (class "Default")
      (node (ref "C8") (pin "2") (pinfunction "2_2") (pintype "input"))
      (node (ref "CN17") (pin "1") (pinfunction "1_1") (pintype "input"))
      (node (ref "P5") (pin "7") (pinfunction "7_7") (pintype "input"))
      (node (ref "SW8") (pin "1") (pinfunction "1_1") (pintype "input"))
      (node (ref "SW8") (pin "2") (pinfunction "2_2") (pintype "input"))
      (node (ref "U3") (pin "5") (pinfunction "5_5") (pintype "input"))
    )
    (net (code "30") (name "WAKE4") (class "Default")
      (node (ref "C11") (pin "2") (pinfunction "2_2") (pintype "input"))
      (node (ref "CN23") (pin "1") (pinfunction "1_1") (pintype "input"))
      (node (ref "P7") (pin "7") (pinfunction "7_7") (pintype "input"))
      (node (ref "SW11") (pin "1") (pinfunction "1_1") (pintype "input"))
      (node (ref "SW11") (pin "2") (pinfunction "2_2") (pintype "input"))
      (node (ref "U4") (pin "5") (pinfunction "5_5") (pintype "input"))
    )
  )
)
